# Colour_Dectector.net
KiCad netlist of a schematic drawn in EAGLE
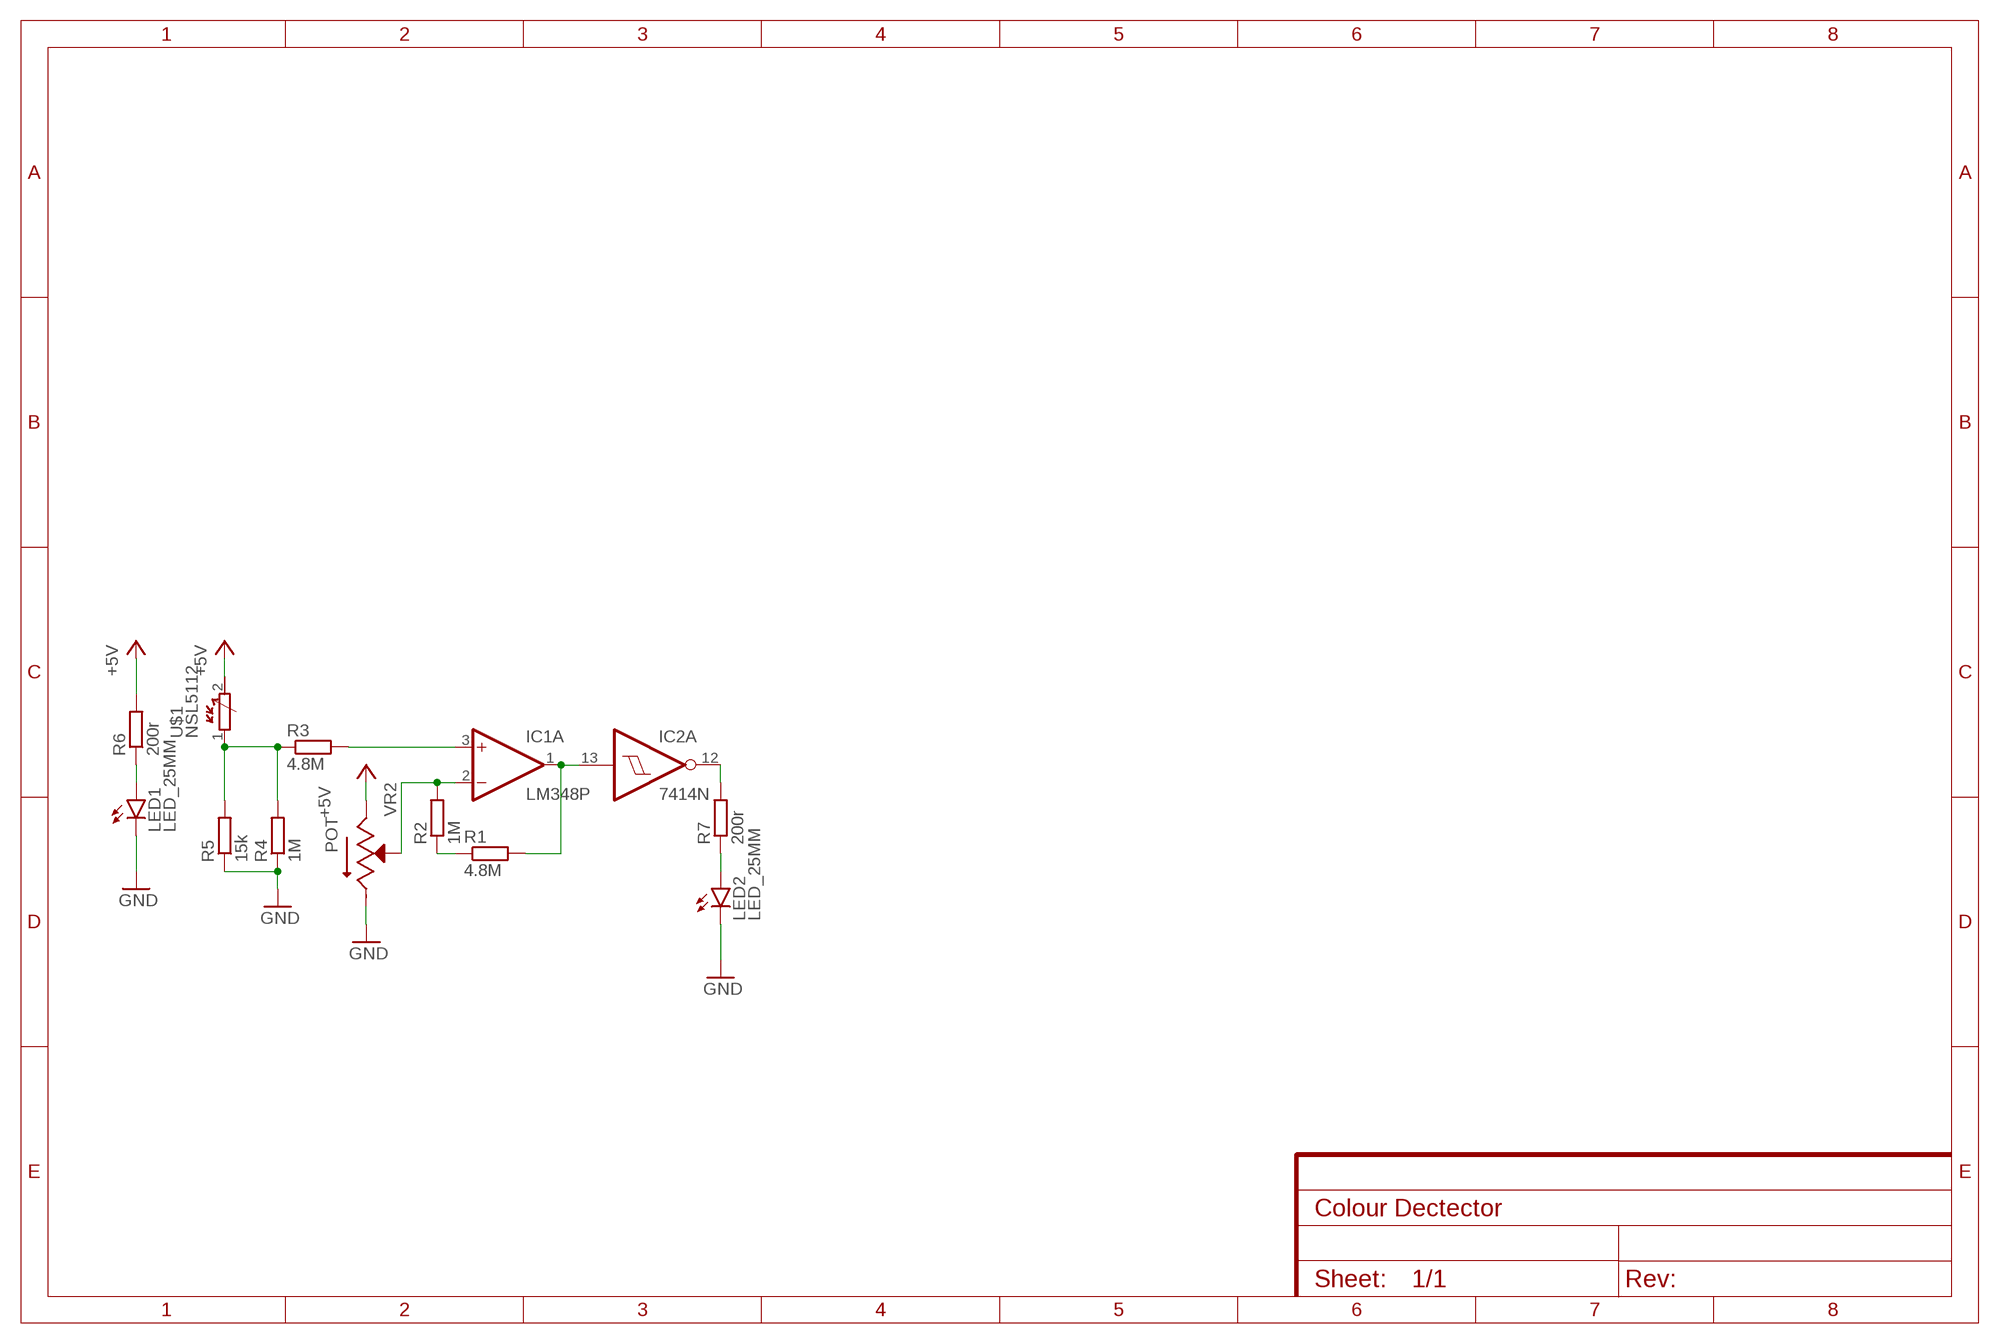
[diagram p0: schematic, sheet 1]

(export (version "E")
  (design (tool "Eeschema 10.0.6"))
  (components
    (comp (ref "IC1")
      (value "LM348P")
      (footprint "eagle-import:DIL14")
      (libsource (lib "eagle-import") (part "LM348P"))
    )
    (comp (ref "IC2")
      (value "7414N")
      (footprint "eagle-import:DIL14")
      (libsource (lib "eagle-import") (part "7414N"))
    )
    (comp (ref "LED1")
      (value "LED_25MM")
      (footprint "eagle-import:LED5MM")
      (libsource (lib "eagle-import") (part "LED_25MM"))
    )
    (comp (ref "LED2")
      (value "LED_25MM")
      (footprint "eagle-import:LED5MM")
      (libsource (lib "eagle-import") (part "LED_25MM"))
    )
    (comp (ref "R1")
      (value "4.8M")
      (footprint "eagle-import:0204_7")
      (libsource (lib "eagle-import") (part "R-EU_0204/7"))
    )
    (comp (ref "R2")
      (value "1M")
      (footprint "eagle-import:0204_7")
      (libsource (lib "eagle-import") (part "R-EU_0204/7"))
    )
    (comp (ref "R3")
      (value "4.8M")
      (footprint "eagle-import:0204_7")
      (libsource (lib "eagle-import") (part "R-EU_0204/7"))
    )
    (comp (ref "R4")
      (value "1M")
      (footprint "eagle-import:0204_7")
      (libsource (lib "eagle-import") (part "R-EU_0204/7"))
    )
    (comp (ref "R5")
      (value "15k")
      (footprint "eagle-import:0204_7")
      (libsource (lib "eagle-import") (part "R-EU_0204/7"))
    )
    (comp (ref "R6")
      (value "200r")
      (footprint "eagle-import:0204_7")
      (libsource (lib "eagle-import") (part "R-EU_0204/7"))
    )
    (comp (ref "R7")
      (value "200r")
      (footprint "eagle-import:0204_7")
      (libsource (lib "eagle-import") (part "R-EU_0204/7"))
    )
    (comp (ref "U$1")
      (value "NSL5112")
      (footprint "eagle-import:KK-156-2")
      (libsource (lib "eagle-import") (part "NSL5112"))
    )
    (comp (ref "VR2")
      (value "POT")
      (footprint "eagle-import:TRIM_3296W-1-250")
      (fields (field (name "MF") "Bourns") (field (name "MP") "3296W-1-250"))
      (libsource (lib "eagle-import") (part "POT"))
    )
  )
  (nets
    (net (code "1") (name "+5V") (class "Default")
      (node (ref "R6") (pin "2") (pinfunction "2_2") (pintype "passive"))
      (node (ref "U$1") (pin "2") (pinfunction "E_2") (pintype "passive"))
      (node (ref "VR2") (pin "1") (pinfunction "CCW_1") (pintype "passive"))
    )
    (net (code "2") (name "GND") (class "Default")
      (node (ref "LED1") (pin "K") (pinfunction "C_K") (pintype "passive"))
      (node (ref "LED2") (pin "K") (pinfunction "C_K") (pintype "passive"))
      (node (ref "R4") (pin "1") (pinfunction "1_1") (pintype "passive"))
      (node (ref "R5") (pin "1") (pinfunction "1_1") (pintype "passive"))
      (node (ref "VR2") (pin "3") (pinfunction "CW_3") (pintype "passive"))
    )
    (net (code "3") (name "Net-(IC1A-+IN)") (class "Default")
      (node (ref "IC1") (pin "3") (pinfunction "+IN_3") (pintype "input"))
      (node (ref "R3") (pin "2") (pinfunction "2_2") (pintype "passive"))
    )
    (net (code "4") (name "Net-(IC1A--IN)") (class "Default")
      (node (ref "IC1") (pin "2") (pinfunction "-IN_2") (pintype "input"))
      (node (ref "R2") (pin "2") (pinfunction "2_2") (pintype "passive"))
      (node (ref "VR2") (pin "2") (pinfunction "WIPER_2") (pintype "passive"))
    )
    (net (code "5") (name "Net-(IC1A-OUT)") (class "Default")
      (node (ref "IC1") (pin "1") (pinfunction "OUT_1") (pintype "output"))
      (node (ref "IC2") (pin "13") (pinfunction "I_13") (pintype "input"))
      (node (ref "R1") (pin "2") (pinfunction "2_2") (pintype "passive"))
    )
    (net (code "6") (name "Net-(IC2A-O)") (class "Default")
      (node (ref "IC2") (pin "12") (pinfunction "O_12") (pintype "output"))
      (node (ref "R7") (pin "2") (pinfunction "2_2") (pintype "passive"))
    )
    (net (code "7") (name "Net-(LED1-PadA)") (class "Default")
      (node (ref "LED1") (pin "A") (pinfunction "A_A") (pintype "passive"))
      (node (ref "R6") (pin "1") (pinfunction "1_1") (pintype "passive"))
    )
    (net (code "8") (name "Net-(LED2-PadA)") (class "Default")
      (node (ref "LED2") (pin "A") (pinfunction "A_A") (pintype "passive"))
      (node (ref "R7") (pin "1") (pinfunction "1_1") (pintype "passive"))
    )
    (net (code "9") (name "Net-(R1-Pad1)") (class "Default")
      (node (ref "R1") (pin "1") (pinfunction "1_1") (pintype "passive"))
      (node (ref "R2") (pin "1") (pinfunction "1_1") (pintype "passive"))
    )
    (net (code "10") (name "Net-(U$1-A)") (class "Default")
      (node (ref "R3") (pin "1") (pinfunction "1_1") (pintype "passive"))
      (node (ref "R4") (pin "2") (pinfunction "2_2") (pintype "passive"))
      (node (ref "R5") (pin "2") (pinfunction "2_2") (pintype "passive"))
      (node (ref "U$1") (pin "1") (pinfunction "A_1") (pintype "passive"))
    )
  )
)
